# eagle-v1_0.net
KiCad netlist of a schematic drawn in EAGLE
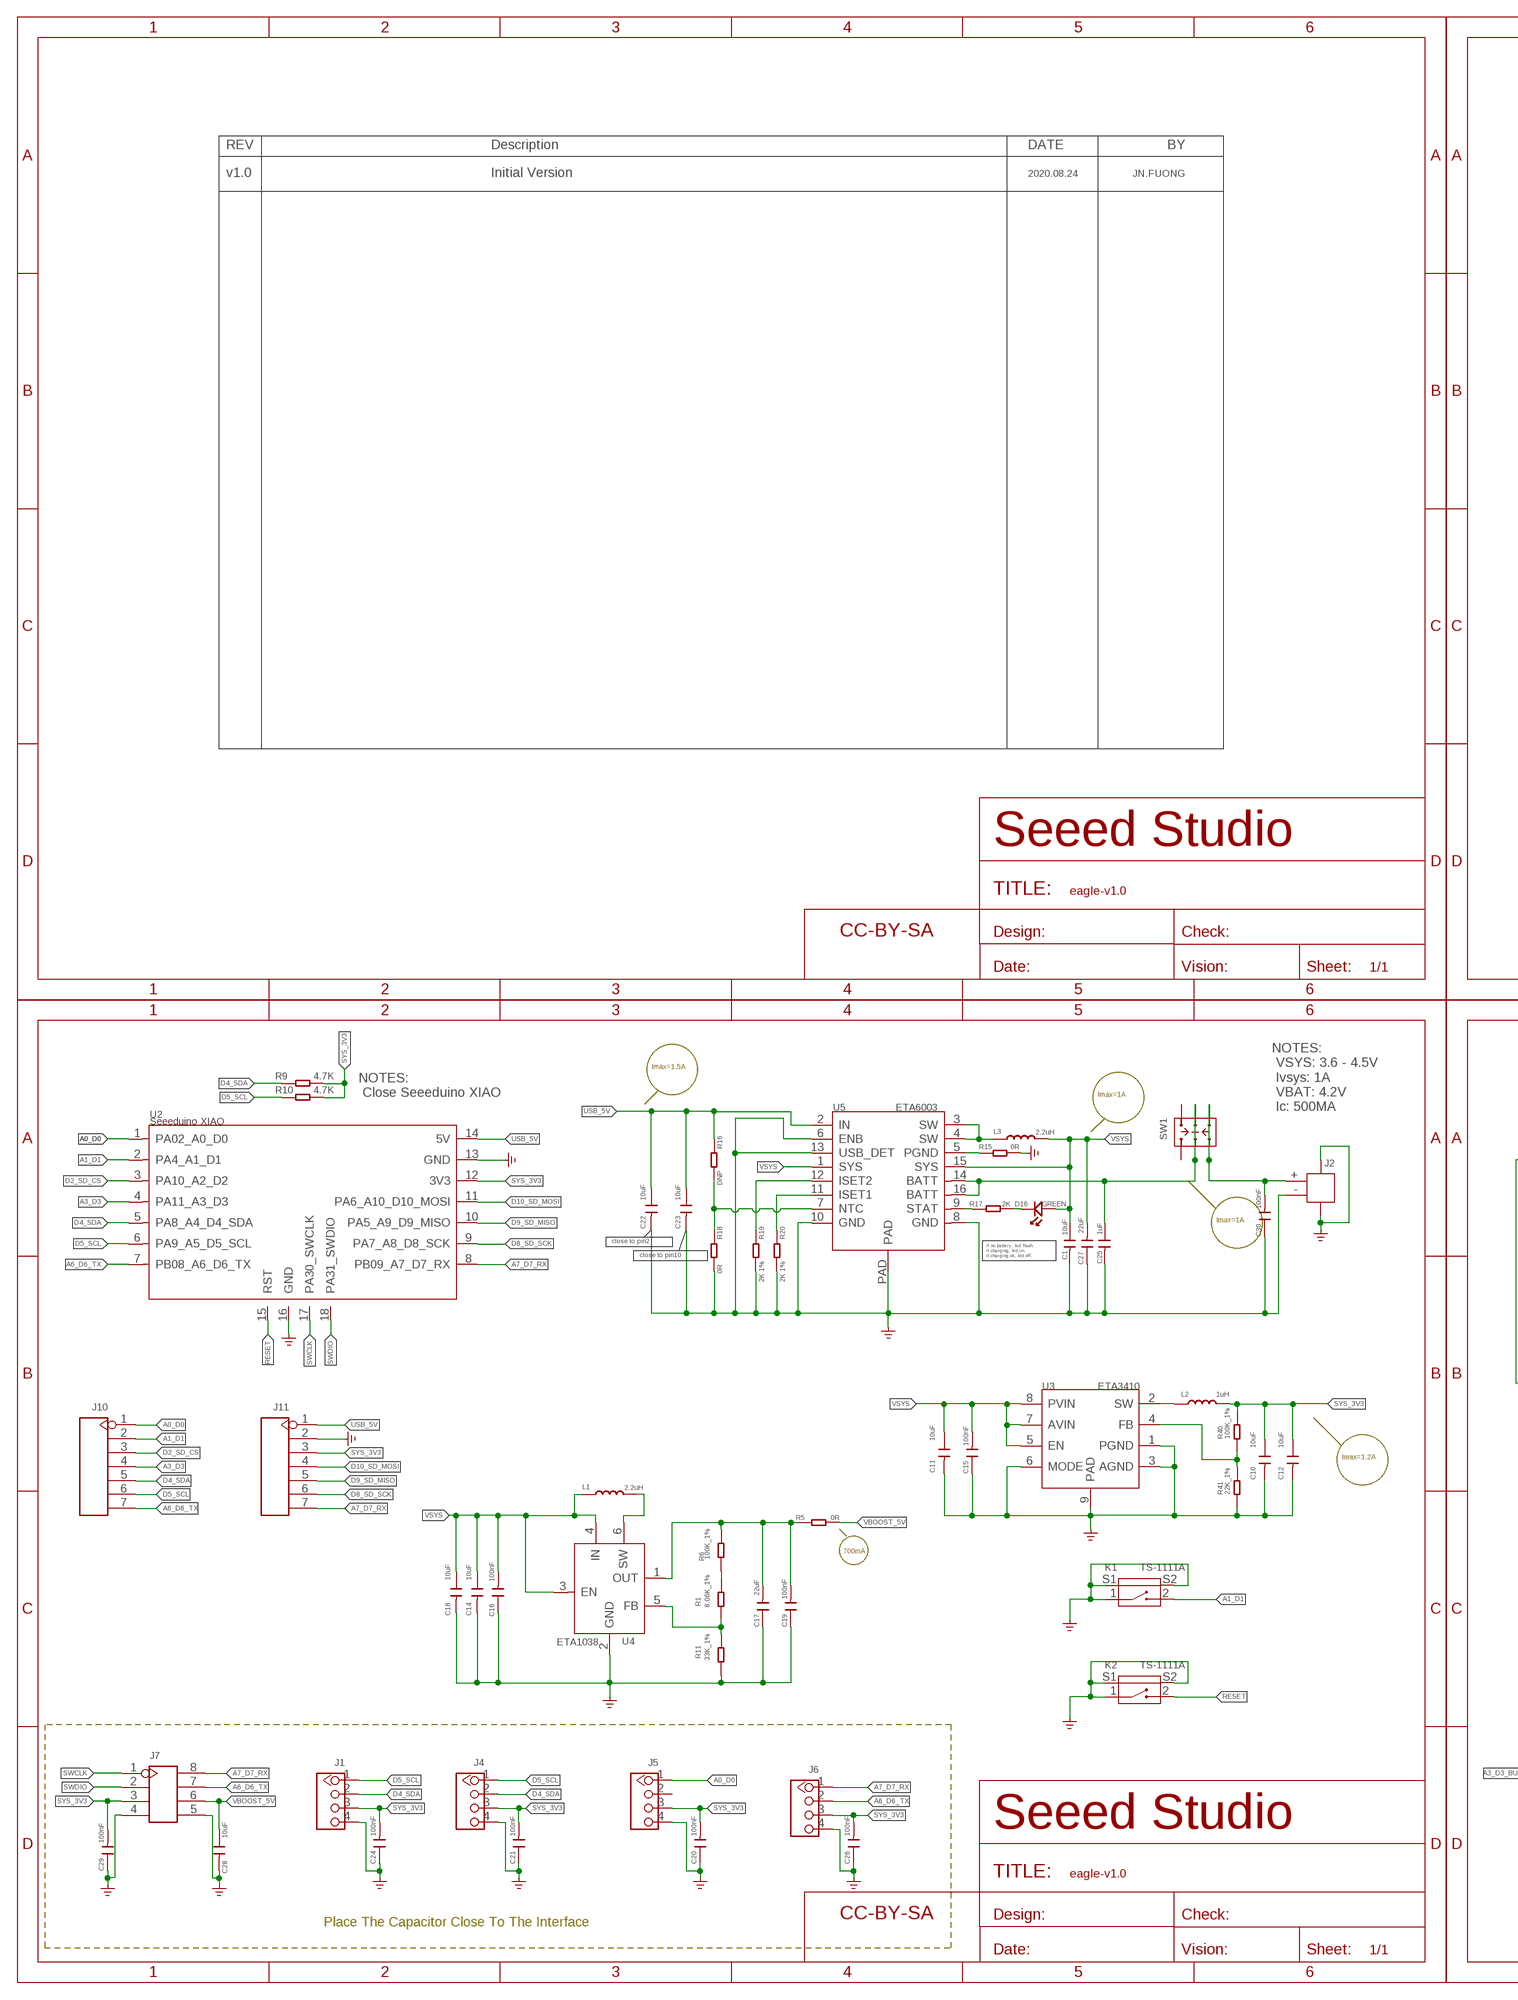
[diagram p0: schematic, sheet 1, part 1 of 2]
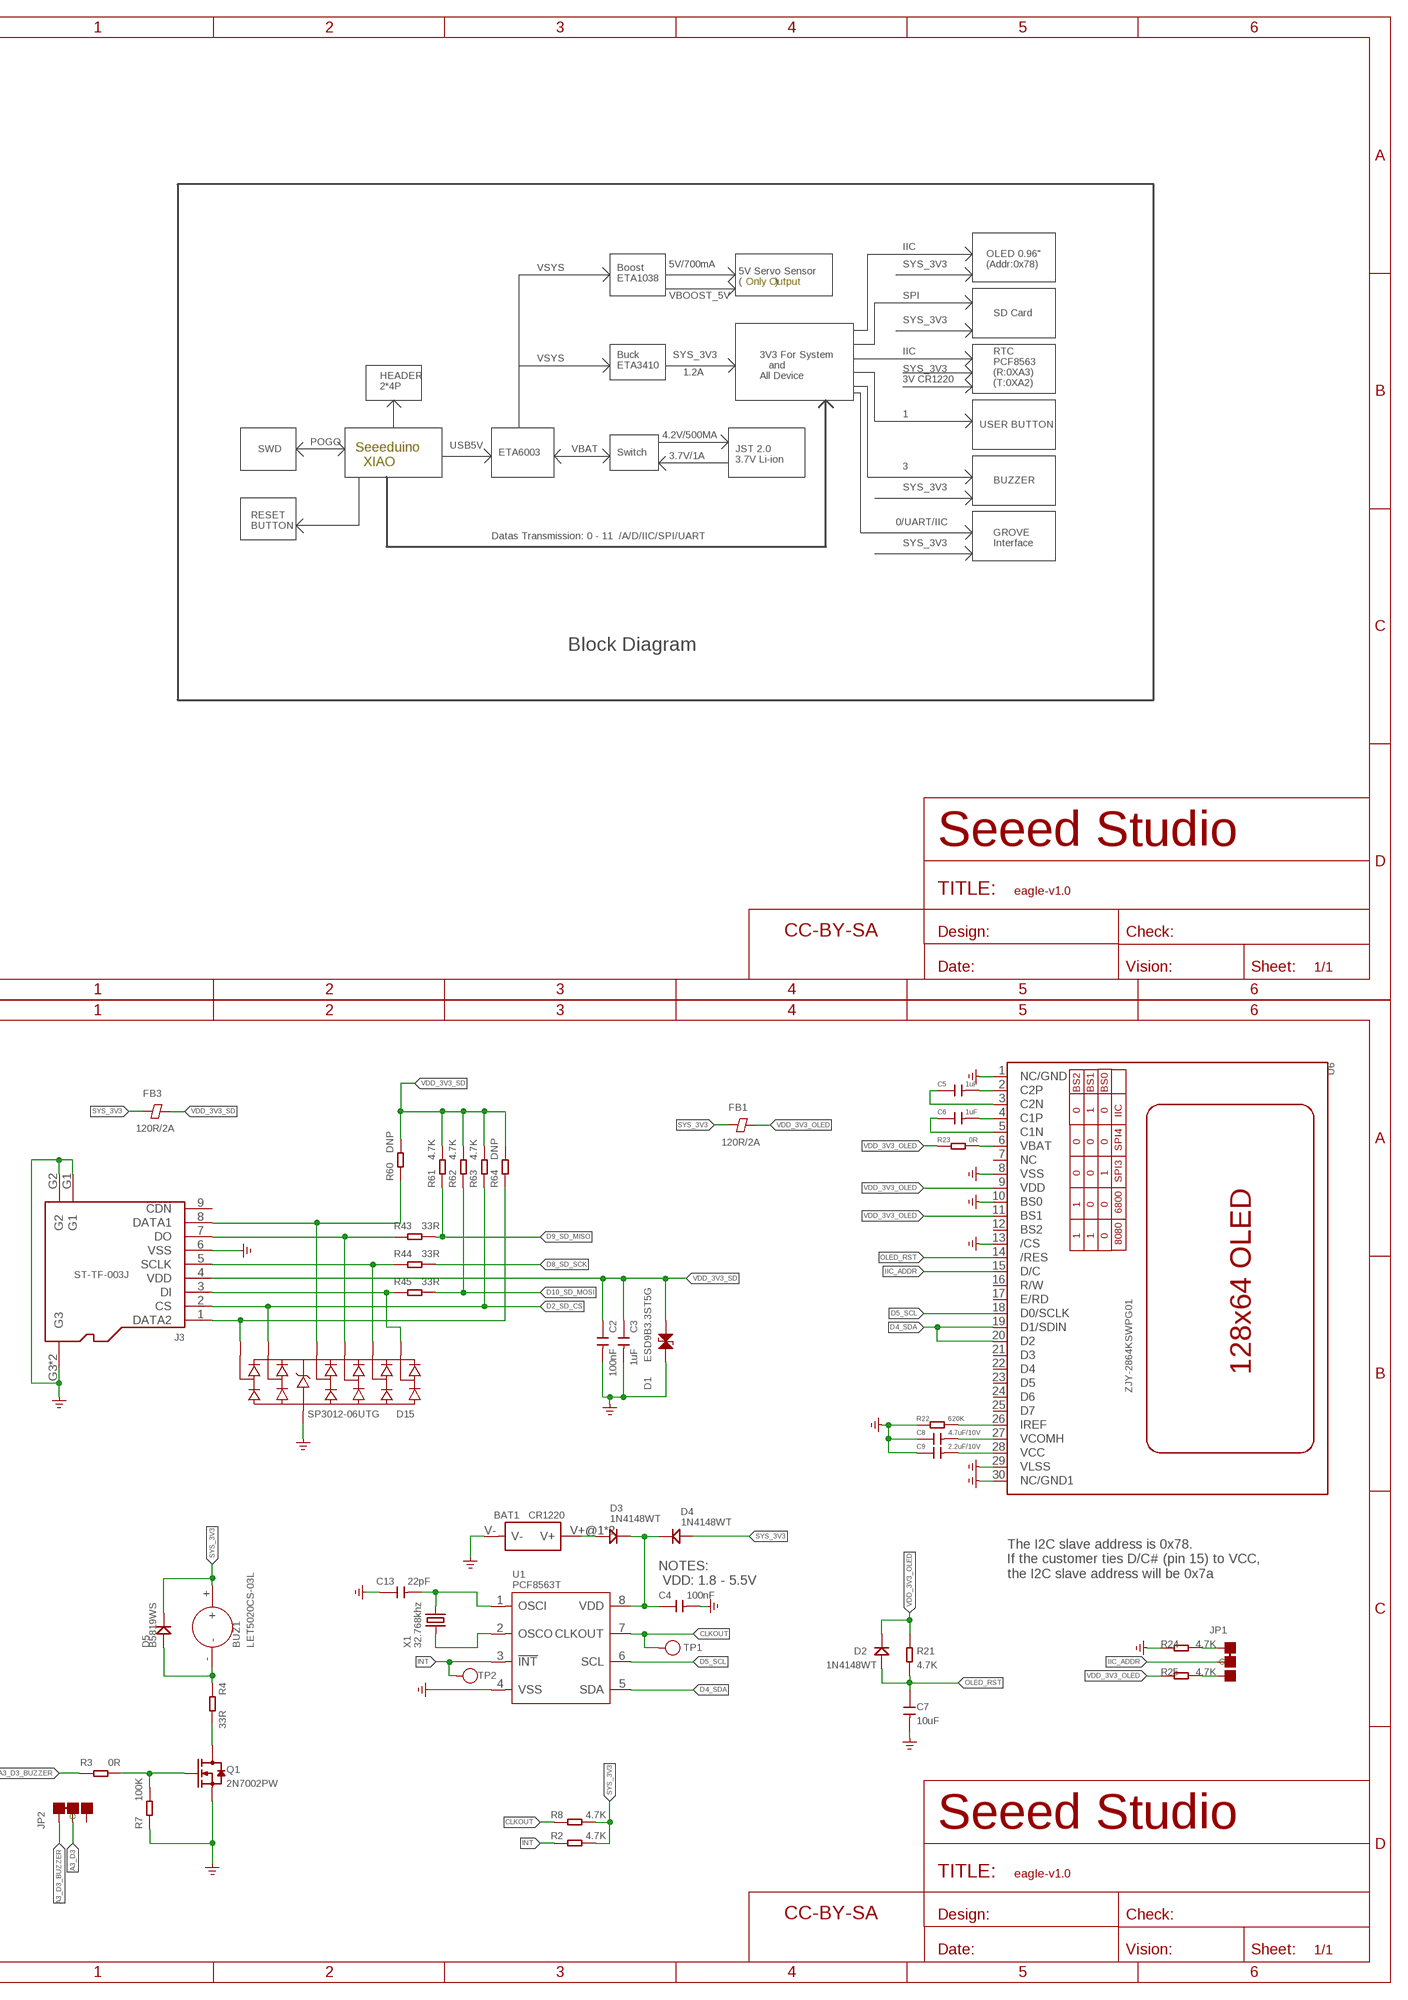
[diagram p1: schematic, sheet 1, part 2 of 2]

(export (version "E")
  (design (tool "Eeschema 10.0.6"))
  (components
    (comp (ref "BAT1")
      (value "CR1220")
      (footprint "eagle-import:BAT2P-SMD-13.2X12.1X3.2MM")
      (libsource (lib "eagle-import") (part "BAT-HOLDER-KST-1206"))
    )
    (comp (ref "BUZ1")
      (value "LET5020CS-03L")
      (footprint "eagle-import:BZ3-SMD-5.0X5.0X2.5MM")
      (libsource (lib "eagle-import") (part "BUZZER-312020004"))
    )
    (comp (ref "C1")
      (value "10uF")
      (footprint "eagle-import:C0603")
      (libsource (lib "eagle-import") (part "C-0603"))
    )
    (comp (ref "C2")
      (value "100nF")
      (footprint "eagle-import:C0402")
      (libsource (lib "eagle-import") (part "C-0402"))
    )
    (comp (ref "C3")
      (value "1uF")
      (footprint "eagle-import:C0402")
      (libsource (lib "eagle-import") (part "C-0402"))
    )
    (comp (ref "C4")
      (value "100nF")
      (footprint "eagle-import:C0402")
      (libsource (lib "eagle-import") (part "C-0402"))
    )
    (comp (ref "C5")
      (value "1uF")
      (footprint "eagle-import:C0402")
      (libsource (lib "eagle-import") (part "C-0402"))
    )
    (comp (ref "C6")
      (value "1uF")
      (footprint "eagle-import:C0402")
      (libsource (lib "eagle-import") (part "C-0402"))
    )
    (comp (ref "C7")
      (value "10uF")
      (footprint "eagle-import:C0603")
      (libsource (lib "eagle-import") (part "C-0603"))
    )
    (comp (ref "C8")
      (value "4.7uF/10V")
      (footprint "eagle-import:C0603")
      (libsource (lib "eagle-import") (part "C-0603"))
    )
    (comp (ref "C9")
      (value "2.2uF/10V")
      (footprint "eagle-import:C0603")
      (libsource (lib "eagle-import") (part "C-0603"))
    )
    (comp (ref "C10")
      (value "10uF")
      (footprint "eagle-import:C0603")
      (libsource (lib "eagle-import") (part "C-0603"))
    )
    (comp (ref "C11")
      (value "10uF")
      (footprint "eagle-import:C0603")
      (libsource (lib "eagle-import") (part "C-0603"))
    )
    (comp (ref "C12")
      (value "10uF")
      (footprint "eagle-import:C0603")
      (libsource (lib "eagle-import") (part "C-0603"))
    )
    (comp (ref "C13")
      (value "22pF")
      (footprint "eagle-import:C0402")
      (libsource (lib "eagle-import") (part "C-0402"))
    )
    (comp (ref "C14")
      (value "10uF")
      (footprint "eagle-import:C0603")
      (libsource (lib "eagle-import") (part "C-0603"))
    )
    (comp (ref "C15")
      (value "100nF")
      (footprint "eagle-import:C0402")
      (libsource (lib "eagle-import") (part "C-0402"))
    )
    (comp (ref "C16")
      (value "100nF")
      (footprint "eagle-import:C0402")
      (libsource (lib "eagle-import") (part "C-0402"))
    )
    (comp (ref "C17")
      (value "22uF")
      (footprint "eagle-import:C0603")
      (libsource (lib "eagle-import") (part "C-0603"))
    )
    (comp (ref "C18")
      (value "10uF")
      (footprint "eagle-import:C0603")
      (libsource (lib "eagle-import") (part "C-0603"))
    )
    (comp (ref "C19")
      (value "100nF")
      (footprint "eagle-import:C0402")
      (libsource (lib "eagle-import") (part "C-0402"))
    )
    (comp (ref "C20")
      (value "100nF")
      (footprint "eagle-import:C0402")
      (libsource (lib "eagle-import") (part "C-0402"))
    )
    (comp (ref "C21")
      (value "100nF")
      (footprint "eagle-import:C0402")
      (libsource (lib "eagle-import") (part "C-0402"))
    )
    (comp (ref "C22")
      (value "10uF")
      (footprint "eagle-import:C0603")
      (libsource (lib "eagle-import") (part "C-0603"))
    )
    (comp (ref "C23")
      (value "10uF")
      (footprint "eagle-import:C0603")
      (libsource (lib "eagle-import") (part "C-0603"))
    )
    (comp (ref "C24")
      (value "100nF")
      (footprint "eagle-import:C0402")
      (libsource (lib "eagle-import") (part "C-0402"))
    )
    (comp (ref "C25")
      (value "1uF")
      (footprint "eagle-import:C0402")
      (libsource (lib "eagle-import") (part "C-0402"))
    )
    (comp (ref "C26")
      (value "100nF")
      (footprint "eagle-import:C0402")
      (libsource (lib "eagle-import") (part "C-0402"))
    )
    (comp (ref "C27")
      (value "22uF")
      (footprint "eagle-import:C0603")
      (libsource (lib "eagle-import") (part "C-0603"))
    )
    (comp (ref "C28")
      (value "10uF")
      (footprint "eagle-import:C0603")
      (libsource (lib "eagle-import") (part "C-0603"))
    )
    (comp (ref "C29")
      (value "100nF")
      (footprint "eagle-import:C0402")
      (libsource (lib "eagle-import") (part "C-0402"))
    )
    (comp (ref "C30")
      (value "100nF")
      (footprint "eagle-import:C0603")
      (libsource (lib "eagle-import") (part "C-0603"))
    )
    (comp (ref "D1")
      (value "ESD9B3.3ST5G")
      (footprint "eagle-import:ESD-0402")
      (libsource (lib "eagle-import") (part "D-ESD-2P-DOUBLE-0402"))
    )
    (comp (ref "D2")
      (value "1N4148WT")
      (footprint "eagle-import:SOD-523")
      (libsource (lib "eagle-import") (part "DIODE'0603'"))
    )
    (comp (ref "D3")
      (value "1N4148WT")
      (footprint "eagle-import:SOD-523")
      (libsource (lib "eagle-import") (part "DIODE'0603'"))
    )
    (comp (ref "D4")
      (value "1N4148WT")
      (footprint "eagle-import:SOD-523")
      (libsource (lib "eagle-import") (part "DIODE'0603'"))
    )
    (comp (ref "D5")
      (value "B5819WS")
      (footprint "eagle-import:SOD-323")
      (libsource (lib "eagle-import") (part "DIODE'0805'"))
    )
    (comp (ref "D15")
      (value "SP3012-06UTG")
      (footprint "eagle-import:UDFN14-0.5-3.5X1.35X0.5MM")
      (libsource (lib "eagle-import") (part "D-ESD-14P"))
    )
    (comp (ref "D16")
      (value "GREEN")
      (footprint "eagle-import:LED-0402")
      (libsource (lib "eagle-import") (part "LED-0402"))
    )
    (comp (ref "FB1")
      (value "120R/2A")
      (footprint "eagle-import:F0402")
      (libsource (lib "eagle-import") (part "FERRITE-BEAD-0402"))
    )
    (comp (ref "FB3")
      (value "120R/2A")
      (footprint "eagle-import:F0402")
      (libsource (lib "eagle-import") (part "FERRITE-BEAD-0402"))
    )
    (comp (ref "FR1")
      (value "SEEEDSTUDIO-OPEN-SCH-FRAME")
      (footprint "eagle-import:SEEEDSTUDIO-PCB-FRAME")
      (libsource (lib "eagle-import") (part "SEEEDSTUDIO-OPEN-SCH-FRAME"))
    )
    (comp (ref "FR2")
      (value "SEEEDSTUDIO-OPEN-SCH-FRAME")
      (footprint "eagle-import:SEEEDSTUDIO-PCB-FRAME")
      (libsource (lib "eagle-import") (part "SEEEDSTUDIO-OPEN-SCH-FRAME"))
    )
    (comp (ref "FR3")
      (value "SEEEDSTUDIO-OPEN-SCH-FRAME")
      (footprint "eagle-import:SEEEDSTUDIO-PCB-FRAME")
      (libsource (lib "eagle-import") (part "SEEEDSTUDIO-OPEN-SCH-FRAME"))
    )
    (comp (ref "FR5")
      (value "SEEEDSTUDIO-OPEN-SCH-FRAME")
      (footprint "eagle-import:SEEEDSTUDIO-PCB-FRAME")
      (libsource (lib "eagle-import") (part "SEEEDSTUDIO-OPEN-SCH-FRAME"))
    )
    (comp (ref "J1")
      (value "GROVE-CONNECTOR-DIP-320110034")
      (footprint "eagle-import:HW4-2.0-90D")
      (libsource (lib "eagle-import") (part "GROVE-CONNECTOR-DIP-320110034"))
    )
    (comp (ref "J2")
      (value "JST-2P-SMD'2.0'")
      (footprint "eagle-import:HW2-SMD-2.0-90D")
      (libsource (lib "eagle-import") (part "JST-2P-SMD'2.0'"))
    )
    (comp (ref "J3")
      (value "ST-TF-003J")
      (footprint "eagle-import:MICRO-SD9+4P-SMD-16.1X14.5X1.85MM")
      (libsource (lib "eagle-import") (part "MICRO-SD-CARD-HOLDER-9P-320090000"))
    )
    (comp (ref "J4")
      (value "GROVE-CONNECTOR-DIP-320110034")
      (footprint "eagle-import:HW4-2.0-90D")
      (libsource (lib "eagle-import") (part "GROVE-CONNECTOR-DIP-320110034"))
    )
    (comp (ref "J5")
      (value "GROVE-CONNECTOR-DIP-320110034")
      (footprint "eagle-import:HW4-2.0-90D")
      (libsource (lib "eagle-import") (part "GROVE-CONNECTOR-DIP-320110034"))
    )
    (comp (ref "J6")
      (value "GROVE-CONNECTOR-DIP-320110034")
      (footprint "eagle-import:HW4-2.0-90D")
      (libsource (lib "eagle-import") (part "GROVE-CONNECTOR-DIP-320110034"))
    )
    (comp (ref "J7")
      (value "HEADER-2X4P-2.54-SMD")
      (footprint "eagle-import:H2X4-SMD-2.54")
      (libsource (lib "eagle-import") (part "HEADER-2X4P-2.54-SMD"))
    )
    (comp (ref "J10")
      (value "HEADER-7P-2.54")
      (footprint "eagle-import:H7-2.54")
      (libsource (lib "eagle-import") (part "HEADER-7P-2.54"))
    )
    (comp (ref "J11")
      (value "HEADER-7P-2.54")
      (footprint "eagle-import:H7-2.54")
      (libsource (lib "eagle-import") (part "HEADER-7P-2.54"))
    )
    (comp (ref "JP1")
      (value "JP-3P-SHORT")
      (footprint "eagle-import:3P-SMD-SHORT")
      (libsource (lib "eagle-import") (part "JP-3P-SHORT"))
    )
    (comp (ref "JP2")
      (value "JP-3P-SHORT")
      (footprint "eagle-import:3P-SMD-SHORT")
      (libsource (lib "eagle-import") (part "JP-3P-SHORT"))
    )
    (comp (ref "K1")
      (value "TS-1111A")
      (footprint "eagle-import:SW4-SMD-4.5X3.8X1.8MM-90D")
      (libsource (lib "eagle-import") (part "BUTTON-2+2P'HQ-TP-1100A'"))
    )
    (comp (ref "K2")
      (value "TS-1111A")
      (footprint "eagle-import:SW4-SMD-4.5X3.8X1.8MM-90D")
      (libsource (lib "eagle-import") (part "BUTTON-2+2P'HQ-TP-1100A'"))
    )
    (comp (ref "L1")
      (value "2.2uH")
      (footprint "eagle-import:L0806")
      (libsource (lib "eagle-import") (part "INDUCTOR/FERRITE-BEAD'0806'"))
    )
    (comp (ref "L2")
      (value "1uH")
      (footprint "eagle-import:L201610")
      (libsource (lib "eagle-import") (part "L-MPM201610SR33_T"))
    )
    (comp (ref "L3")
      (value "2.2uH")
      (footprint "eagle-import:L0806")
      (libsource (lib "eagle-import") (part "INDUCTOR/FERRITE-BEAD'0806'"))
    )
    (comp (ref "Q1")
      (value "2N7002PW")
      (footprint "eagle-import:SOT-323")
      (libsource (lib "eagle-import") (part "MOSFET-N-SI1304BDL"))
    )
    (comp (ref "R1")
      (value "8.06K_1%")
      (footprint "eagle-import:R0402")
      (libsource (lib "eagle-import") (part "R-0402"))
    )
    (comp (ref "R2")
      (value "4.7K")
      (footprint "eagle-import:R0402")
      (libsource (lib "eagle-import") (part "R-0402"))
    )
    (comp (ref "R3")
      (value "0R")
      (footprint "eagle-import:R0402")
      (libsource (lib "eagle-import") (part "R-0402"))
    )
    (comp (ref "R4")
      (value "33R")
      (footprint "eagle-import:R0402")
      (libsource (lib "eagle-import") (part "R-0402"))
    )
    (comp (ref "R5")
      (value "0R")
      (footprint "eagle-import:R0603")
      (libsource (lib "eagle-import") (part "R-0603"))
    )
    (comp (ref "R6")
      (value "100K_1%")
      (footprint "eagle-import:R0402")
      (libsource (lib "eagle-import") (part "R-0402"))
    )
    (comp (ref "R7")
      (value "100K")
      (footprint "eagle-import:R0402")
      (libsource (lib "eagle-import") (part "R-0402"))
    )
    (comp (ref "R8")
      (value "4.7K")
      (footprint "eagle-import:R0402")
      (libsource (lib "eagle-import") (part "R-0402"))
    )
    (comp (ref "R9")
      (value "4.7K")
      (footprint "eagle-import:R0402")
      (libsource (lib "eagle-import") (part "R-0402"))
    )
    (comp (ref "R10")
      (value "4.7K")
      (footprint "eagle-import:R0402")
      (libsource (lib "eagle-import") (part "R-0402"))
    )
    (comp (ref "R11")
      (value "33K_1%")
      (footprint "eagle-import:R0402")
      (libsource (lib "eagle-import") (part "R-0402"))
    )
    (comp (ref "R15")
      (value "0R")
      (footprint "eagle-import:R0402")
      (libsource (lib "eagle-import") (part "R-0402"))
    )
    (comp (ref "R16")
      (value "DNP")
      (footprint "eagle-import:R0402")
      (libsource (lib "eagle-import") (part "R-0402"))
    )
    (comp (ref "R17")
      (value "2K")
      (footprint "eagle-import:R0402")
      (libsource (lib "eagle-import") (part "R-0402"))
    )
    (comp (ref "R18")
      (value "0R")
      (footprint "eagle-import:R0402")
      (libsource (lib "eagle-import") (part "R-0402"))
    )
    (comp (ref "R19")
      (value "2K 1%")
      (footprint "eagle-import:R0402")
      (libsource (lib "eagle-import") (part "R-0402"))
    )
    (comp (ref "R20")
      (value "2K 1%")
      (footprint "eagle-import:R0402")
      (libsource (lib "eagle-import") (part "R-0402"))
    )
    (comp (ref "R21")
      (value "4.7K")
      (footprint "eagle-import:R0402")
      (libsource (lib "eagle-import") (part "R-0402"))
    )
    (comp (ref "R22")
      (value "620K")
      (footprint "eagle-import:R0402")
      (libsource (lib "eagle-import") (part "R-0402"))
    )
    (comp (ref "R23")
      (value "0R")
      (footprint "eagle-import:R0402")
      (libsource (lib "eagle-import") (part "R-0402"))
    )
    (comp (ref "R24")
      (value "4.7K")
      (footprint "eagle-import:R0402")
      (libsource (lib "eagle-import") (part "R-0402"))
    )
    (comp (ref "R25")
      (value "4.7K")
      (footprint "eagle-import:R0402")
      (libsource (lib "eagle-import") (part "R-0402"))
    )
    (comp (ref "R40")
      (value "100K_1%")
      (footprint "eagle-import:R0402")
      (libsource (lib "eagle-import") (part "R-0402"))
    )
    (comp (ref "R41")
      (value "22K_1%")
      (footprint "eagle-import:R0402")
      (libsource (lib "eagle-import") (part "R-0402"))
    )
    (comp (ref "R43")
      (value "33R")
      (footprint "eagle-import:R0402")
      (libsource (lib "eagle-import") (part "R-0402"))
    )
    (comp (ref "R44")
      (value "33R")
      (footprint "eagle-import:R0402")
      (libsource (lib "eagle-import") (part "R-0402"))
    )
    (comp (ref "R45")
      (value "33R")
      (footprint "eagle-import:R0402")
      (libsource (lib "eagle-import") (part "R-0402"))
    )
    (comp (ref "R60")
      (value "DNP")
      (footprint "eagle-import:R0402")
      (libsource (lib "eagle-import") (part "R-0402"))
    )
    (comp (ref "R61")
      (value "4.7K")
      (footprint "eagle-import:R0402")
      (libsource (lib "eagle-import") (part "R-0402"))
    )
    (comp (ref "R62")
      (value "4.7K")
      (footprint "eagle-import:R0402")
      (libsource (lib "eagle-import") (part "R-0402"))
    )
    (comp (ref "R63")
      (value "4.7K")
      (footprint "eagle-import:R0402")
      (libsource (lib "eagle-import") (part "R-0402"))
    )
    (comp (ref "R64")
      (value "DNP")
      (footprint "eagle-import:R0402")
      (libsource (lib "eagle-import") (part "R-0402"))
    )
    (comp (ref "SW1")
      (value "SWITCH-2CH-6P-311030004")
      (footprint "eagle-import:SW6-2.54-9.0X3.5X3.2MM-90D")
      (libsource (lib "eagle-import") (part "SWITCH-2CH-6P-311030004"))
    )
    (comp (ref "TP1")
      (value "TEST-POINT'4545'")
      (footprint "eagle-import:TP-D45MIL")
      (fields (field (name "PARTNO") "DNP"))
      (libsource (lib "eagle-import") (part "TEST-POINT'4545'"))
    )
    (comp (ref "TP2")
      (value "TEST-POINT'4545'")
      (footprint "eagle-import:TP-D45MIL")
      (fields (field (name "PARTNO") "DNP"))
      (libsource (lib "eagle-import") (part "TEST-POINT'4545'"))
    )
    (comp (ref "U1")
      (value "PCF8563T")
      (footprint "eagle-import:SOP8-1.27-5X3.9MM")
      (libsource (lib "eagle-import") (part "RTC-PCF8563T"))
    )
    (comp (ref "U2")
      (value "Seeeduino XIAO")
      (footprint "eagle-import:MOUDLE14P-2.54-21X17.8MM-TEST")
      (libsource (lib "eagle-import") (part "MOUDLE-SEEEDUINO-XIAO-TEST-DIP"))
    )
    (comp (ref "U3")
      (value "ETA3410")
      (footprint "eagle-import:DFN8G-0.5-2X2MM")
      (libsource (lib "eagle-import") (part "CONVERTER-ETA3410"))
    )
    (comp (ref "U4")
      (value "ETA1038")
      (footprint "eagle-import:SOT-23-6")
      (libsource (lib "eagle-import") (part "CONVERTER-ETA1038"))
    )
    (comp (ref "U5")
      (value "ETA6003")
      (footprint "eagle-import:QFN16GA-0.5-3X3MM")
      (libsource (lib "eagle-import") (part "PMIC-ETA6003-310990023"))
    )
    (comp (ref "U6")
      (value "ZJY-2864KSWPG01")
      (footprint "eagle-import:OLED30P-0.7-24.74X16.9MM")
      (libsource (lib "eagle-import") (part "OLED-12864-30P"))
    )
    (comp (ref "X1")
      (value "32.768khz")
      (footprint "eagle-import:X2-SMD-L2.0X1.2X0.55MM")
      (libsource (lib "eagle-import") (part "CRYSTAL-2P'NX2012SA'"))
    )
  )
  (nets
    (net (code "1") (name "A0_D0") (class "Default")
      (node (ref "J10") (pin "1") (pinfunction "1_1") (pintype "bidirectional"))
      (node (ref "J5") (pin "1") (pinfunction "1_1") (pintype "bidirectional"))
      (node (ref "U2") (pin "1") (pinfunction "PA02_A0_D0_1") (pintype "bidirectional"))
    )
    (net (code "2") (name "A1_D1") (class "Default")
      (node (ref "J10") (pin "2") (pinfunction "2_2") (pintype "bidirectional"))
      (node (ref "K1") (pin "2") (pinfunction "2_2") (pintype "bidirectional"))
      (node (ref "U2") (pin "2") (pinfunction "PA4_A1_D1_2") (pintype "bidirectional"))
    )
    (net (code "3") (name "A3_D3") (class "Default")
      (node (ref "J10") (pin "4") (pinfunction "4_4") (pintype "bidirectional"))
      (node (ref "JP2") (pin "MM") (pinfunction "C_MM") (pintype "bidirectional"))
      (node (ref "U2") (pin "4") (pinfunction "PA11_A3_D3_4") (pintype "bidirectional"))
    )
    (net (code "4") (name "A3_D3_BUZZER") (class "Default")
      (node (ref "JP2") (pin "11") (pinfunction "L_11") (pintype "bidirectional"))
      (node (ref "R3") (pin "1") (pinfunction "1_1") (pintype "passive"))
    )
    (net (code "5") (name "A6_D6_TX") (class "Default")
      (node (ref "J10") (pin "7") (pinfunction "7_7") (pintype "bidirectional"))
      (node (ref "J6") (pin "2") (pinfunction "2_2") (pintype "bidirectional"))
      (node (ref "J7") (pin "7") (pinfunction "7_7") (pintype "bidirectional"))
      (node (ref "U2") (pin "7") (pinfunction "PB08_A6_D6_TX_7") (pintype "bidirectional"))
    )
    (net (code "6") (name "A7_D7_RX") (class "Default")
      (node (ref "J11") (pin "7") (pinfunction "7_7") (pintype "bidirectional"))
      (node (ref "J6") (pin "1") (pinfunction "1_1") (pintype "bidirectional"))
      (node (ref "J7") (pin "8") (pinfunction "8_8") (pintype "bidirectional"))
      (node (ref "U2") (pin "8") (pinfunction "PB09_A7_D7_RX_8") (pintype "bidirectional"))
    )
    (net (code "7") (name "CLKOUT") (class "Default")
      (node (ref "R8") (pin "1") (pinfunction "1_1") (pintype "passive"))
      (node (ref "TP1") (pin "T") (pinfunction "T_T") (pintype "bidirectional"))
      (node (ref "U1") (pin "7") (pinfunction "CLKOUT_7") (pintype "bidirectional"))
    )
    (net (code "8") (name "D2_SD_CS") (class "Default")
      (node (ref "D15") (pin "6") (pinfunction "9_6") (pintype "bidirectional"))
      (node (ref "D15") (pin "9") (pinfunction "9_9") (pintype "bidirectional"))
      (node (ref "J10") (pin "3") (pinfunction "3_3") (pintype "bidirectional"))
      (node (ref "J3") (pin "2") (pinfunction "CS_2") (pintype "bidirectional"))
      (node (ref "R63") (pin "1") (pinfunction "1_1") (pintype "passive"))
      (node (ref "U2") (pin "3") (pinfunction "PA10_A2_D2_3") (pintype "bidirectional"))
    )
    (net (code "9") (name "D4_SDA") (class "Default")
      (node (ref "J1") (pin "2") (pinfunction "2_2") (pintype "bidirectional"))
      (node (ref "J10") (pin "5") (pinfunction "5_5") (pintype "bidirectional"))
      (node (ref "J4") (pin "2") (pinfunction "2_2") (pintype "bidirectional"))
      (node (ref "R9") (pin "1") (pinfunction "1_1") (pintype "passive"))
      (node (ref "U1") (pin "5") (pinfunction "SDA_5") (pintype "bidirectional"))
      (node (ref "U2") (pin "5") (pinfunction "PA8_A4_D4_SDA_5") (pintype "bidirectional"))
      (node (ref "U6") (pin "19") (pinfunction "D1/SDIN_19") (pintype "bidirectional"))
      (node (ref "U6") (pin "20") (pinfunction "D2_20") (pintype "input"))
    )
    (net (code "10") (name "D5_SCL") (class "Default")
      (node (ref "J1") (pin "1") (pinfunction "1_1") (pintype "bidirectional"))
      (node (ref "J10") (pin "6") (pinfunction "6_6") (pintype "bidirectional"))
      (node (ref "J4") (pin "1") (pinfunction "1_1") (pintype "bidirectional"))
      (node (ref "R10") (pin "1") (pinfunction "1_1") (pintype "passive"))
      (node (ref "U1") (pin "6") (pinfunction "SCL_6") (pintype "bidirectional"))
      (node (ref "U2") (pin "6") (pinfunction "PA9_A5_D5_SCL_6") (pintype "bidirectional"))
      (node (ref "U6") (pin "18") (pinfunction "D0/SCLK_18") (pintype "bidirectional"))
    )
    (net (code "11") (name "D8_SD_SCK") (class "Default")
      (node (ref "J11") (pin "6") (pinfunction "6_6") (pintype "bidirectional"))
      (node (ref "R44") (pin "2") (pinfunction "2_2") (pintype "passive"))
      (node (ref "U2") (pin "9") (pinfunction "PA7_A8_D8_SCK_9") (pintype "bidirectional"))
    )
    (net (code "12") (name "D9_SD_MISO") (class "Default")
      (node (ref "J11") (pin "5") (pinfunction "5_5") (pintype "bidirectional"))
      (node (ref "R43") (pin "2") (pinfunction "2_2") (pintype "passive"))
      (node (ref "R61") (pin "1") (pinfunction "1_1") (pintype "passive"))
      (node (ref "U2") (pin "10") (pinfunction "PA5_A9_D9_MISO_10") (pintype "bidirectional"))
    )
    (net (code "13") (name "D10_SD_MOSI") (class "Default")
      (node (ref "J11") (pin "4") (pinfunction "4_4") (pintype "bidirectional"))
      (node (ref "R45") (pin "2") (pinfunction "2_2") (pintype "passive"))
      (node (ref "R62") (pin "1") (pinfunction "1_1") (pintype "passive"))
      (node (ref "U2") (pin "11") (pinfunction "PA6_A10_D10_MOSI_11") (pintype "bidirectional"))
    )
    (net (code "14") (name "GND_POWER") (class "Default")
      (node (ref "BAT1") (pin "V-") (pinfunction "V-_V-") (pintype "bidirectional"))
      (node (ref "C1") (pin "2") (pinfunction "2_2") (pintype "passive"))
      (node (ref "C10") (pin "2") (pinfunction "2_2") (pintype "passive"))
      (node (ref "C11") (pin "2") (pinfunction "2_2") (pintype "passive"))
      (node (ref "C12") (pin "2") (pinfunction "2_2") (pintype "passive"))
      (node (ref "C13") (pin "1") (pinfunction "1_1") (pintype "passive"))
      (node (ref "C14") (pin "2") (pinfunction "2_2") (pintype "passive"))
      (node (ref "C15") (pin "1") (pinfunction "1_1") (pintype "passive"))
      (node (ref "C16") (pin "1") (pinfunction "1_1") (pintype "passive"))
      (node (ref "C17") (pin "1") (pinfunction "1_1") (pintype "passive"))
      (node (ref "C18") (pin "2") (pinfunction "2_2") (pintype "passive"))
      (node (ref "C19") (pin "1") (pinfunction "1_1") (pintype "passive"))
      (node (ref "C2") (pin "2") (pinfunction "2_2") (pintype "passive"))
      (node (ref "C20") (pin "1") (pinfunction "1_1") (pintype "passive"))
      (node (ref "C21") (pin "1") (pinfunction "1_1") (pintype "passive"))
      (node (ref "C22") (pin "2") (pinfunction "2_2") (pintype "passive"))
      (node (ref "C23") (pin "2") (pinfunction "2_2") (pintype "passive"))
      (node (ref "C24") (pin "1") (pinfunction "1_1") (pintype "passive"))
      (node (ref "C25") (pin "2") (pinfunction "2_2") (pintype "passive"))
      (node (ref "C26") (pin "1") (pinfunction "1_1") (pintype "passive"))
      (node (ref "C27") (pin "1") (pinfunction "1_1") (pintype "passive"))
      (node (ref "C28") (pin "2") (pinfunction "2_2") (pintype "passive"))
      (node (ref "C29") (pin "1") (pinfunction "1_1") (pintype "passive"))
      (node (ref "C3") (pin "2") (pinfunction "2_2") (pintype "passive"))
      (node (ref "C30") (pin "1") (pinfunction "1_1") (pintype "passive"))
      (node (ref "C4") (pin "2") (pinfunction "2_2") (pintype "passive"))
      (node (ref "C7") (pin "2") (pinfunction "2_2") (pintype "passive"))
      (node (ref "C8") (pin "1") (pinfunction "1_1") (pintype "passive"))
      (node (ref "C9") (pin "1") (pinfunction "1_1") (pintype "passive"))
      (node (ref "D1") (pin "1") (pinfunction "1_1") (pintype "bidirectional"))
      (node (ref "D15") (pin "10") (pinfunction "10_10") (pintype "bidirectional"))
      (node (ref "D15") (pin "5") (pinfunction "10_5") (pintype "bidirectional"))
      (node (ref "J1") (pin "4") (pinfunction "4_4") (pintype "bidirectional"))
      (node (ref "J11") (pin "2") (pinfunction "2_2") (pintype "bidirectional"))
      (node (ref "J2") (pin "-") (pinfunction "2_-") (pintype "bidirectional"))
      (node (ref "J2") (pin "3") (pinfunction "3_3") (pintype "bidirectional"))
      (node (ref "J2") (pin "4") (pinfunction "4_4") (pintype "bidirectional"))
      (node (ref "J3") (pin "6") (pinfunction "VSS_6") (pintype "bidirectional"))
      (node (ref "J3") (pin "G1") (pinfunction "G1_G1") (pintype "bidirectional"))
      (node (ref "J3") (pin "G2") (pinfunction "G2_G2") (pintype "bidirectional"))
      (node (ref "J3") (pin "G3") (pinfunction "G3_G3") (pintype "bidirectional"))
      (node (ref "J3") (pin "G4") (pinfunction "G3_G4") (pintype "bidirectional"))
      (node (ref "J4") (pin "4") (pinfunction "4_4") (pintype "bidirectional"))
      (node (ref "J5") (pin "4") (pinfunction "4_4") (pintype "bidirectional"))
      (node (ref "J6") (pin "4") (pinfunction "4_4") (pintype "bidirectional"))
      (node (ref "J7") (pin "4") (pinfunction "4_4") (pintype "bidirectional"))
      (node (ref "J7") (pin "5") (pinfunction "5_5") (pintype "bidirectional"))
      (node (ref "K1") (pin "1") (pinfunction "1_1") (pintype "bidirectional"))
      (node (ref "K1") (pin "S1") (pinfunction "S1_S1") (pintype "bidirectional"))
      (node (ref "K1") (pin "S2") (pinfunction "S2_S2") (pintype "bidirectional"))
      (node (ref "K2") (pin "1") (pinfunction "1_1") (pintype "bidirectional"))
      (node (ref "K2") (pin "S1") (pinfunction "S1_S1") (pintype "bidirectional"))
      (node (ref "K2") (pin "S2") (pinfunction "S2_S2") (pintype "bidirectional"))
      (node (ref "Q1") (pin "2") (pinfunction "S_2") (pintype "passive"))
      (node (ref "R11") (pin "2") (pinfunction "2_2") (pintype "passive"))
      (node (ref "R15") (pin "2") (pinfunction "2_2") (pintype "passive"))
      (node (ref "R18") (pin "2") (pinfunction "2_2") (pintype "passive"))
      (node (ref "R19") (pin "2") (pinfunction "2_2") (pintype "passive"))
      (node (ref "R20") (pin "2") (pinfunction "2_2") (pintype "passive"))
      (node (ref "R22") (pin "2") (pinfunction "2_2") (pintype "passive"))
      (node (ref "R24") (pin "1") (pinfunction "1_1") (pintype "passive"))
      (node (ref "R41") (pin "1") (pinfunction "1_1") (pintype "passive"))
      (node (ref "R7") (pin "1") (pinfunction "1_1") (pintype "passive"))
      (node (ref "U1") (pin "4") (pinfunction "VSS_4") (pintype "bidirectional"))
      (node (ref "U2") (pin "13") (pinfunction "GND_13") (pintype "bidirectional"))
      (node (ref "U2") (pin "16") (pinfunction "GND_16") (pintype "bidirectional"))
      (node (ref "U3") (pin "1") (pinfunction "PGND_1") (pintype "bidirectional"))
      (node (ref "U3") (pin "3") (pinfunction "AGND_3") (pintype "bidirectional"))
      (node (ref "U3") (pin "6") (pinfunction "MODE_6") (pintype "bidirectional"))
      (node (ref "U3") (pin "9") (pinfunction "PAD_9") (pintype "bidirectional"))
      (node (ref "U4") (pin "2") (pinfunction "GND_2") (pintype "bidirectional"))
      (node (ref "U5") (pin "10") (pinfunction "GND_10") (pintype "bidirectional"))
      (node (ref "U5") (pin "13") (pinfunction "USB_DET_13") (pintype "bidirectional"))
      (node (ref "U5") (pin "6") (pinfunction "ENB_6") (pintype "bidirectional"))
      (node (ref "U5") (pin "8") (pinfunction "GND_8") (pintype "bidirectional"))
      (node (ref "U5") (pin "PAD") (pinfunction "PAD_PAD") (pintype "bidirectional"))
      (node (ref "U6") (pin "1") (pinfunction "NC/GND_1") (pintype "input"))
      (node (ref "U6") (pin "10") (pinfunction "BS0_10") (pintype "input"))
      (node (ref "U6") (pin "13") (pinfunction "/CS_13") (pintype "input"))
      (node (ref "U6") (pin "29") (pinfunction "VLSS_29") (pintype "power_in"))
      (node (ref "U6") (pin "30") (pinfunction "NC/GND1_30") (pintype "input"))
      (node (ref "U6") (pin "8") (pinfunction "VSS_8") (pintype "power_in"))
    )
    (net (code "15") (name "IIC_ADDR") (class "Default")
      (node (ref "JP1") (pin "MM") (pinfunction "C_MM") (pintype "bidirectional"))
      (node (ref "U6") (pin "15") (pinfunction "D/C_15") (pintype "input"))
    )
    (net (code "16") (name "INT") (class "Default")
      (node (ref "R2") (pin "1") (pinfunction "1_1") (pintype "passive"))
      (node (ref "TP2") (pin "T") (pinfunction "T_T") (pintype "bidirectional"))
      (node (ref "U1") (pin "3") (pinfunction "~{INT}_3") (pintype "bidirectional"))
    )
    (net (code "17") (name "Net-(BAT1-V+-PadV+@1)") (class "Default")
      (node (ref "BAT1") (pin "V+@1") (pinfunction "V+_V+@1") (pintype "bidirectional"))
      (node (ref "BAT1") (pin "V+@2") (pinfunction "V+_V+@2") (pintype "bidirectional"))
      (node (ref "D3") (pin "+") (pinfunction "+_+") (pintype "passive"))
    )
    (net (code "18") (name "Net-(BUZ1-Pad-)") (class "Default")
      (node (ref "BUZ1") (pin "-") (pinfunction "-_-") (pintype "bidirectional"))
      (node (ref "D5") (pin "+") (pinfunction "+_+") (pintype "passive"))
      (node (ref "R4") (pin "1") (pinfunction "1_1") (pintype "passive"))
    )
    (net (code "19") (name "Net-(C25-Pad1)") (class "Default")
      (node (ref "C25") (pin "1") (pinfunction "1_1") (pintype "passive"))
      (node (ref "SW1") (pin "COM1") (pinfunction "COM1_COM1") (pintype "bidirectional"))
      (node (ref "SW1") (pin "COM2") (pinfunction "COM2_COM2") (pintype "bidirectional"))
      (node (ref "U5") (pin "14") (pinfunction "BATT_14") (pintype "bidirectional"))
      (node (ref "U5") (pin "16") (pinfunction "BATT_16") (pintype "bidirectional"))
    )
    (net (code "20") (name "Net-(D16-Pad-)") (class "Default")
      (node (ref "D16") (pin "-") (pinfunction "-_-") (pintype "passive"))
      (node (ref "R17") (pin "1") (pinfunction "1_1") (pintype "passive"))
    )
    (net (code "21") (name "Net-(J2-1)") (class "Default")
      (node (ref "C30") (pin "2") (pinfunction "2_2") (pintype "passive"))
      (node (ref "J2") (pin "+") (pinfunction "1_+") (pintype "bidirectional"))
      (node (ref "SW1") (pin "CH1B") (pinfunction "CH1B_CH1B") (pintype "bidirectional"))
      (node (ref "SW1") (pin "CH2B") (pinfunction "CH2B_CH2B") (pintype "bidirectional"))
    )
    (net (code "22") (name "Net-(J3-DATA1)") (class "Default")
      (node (ref "D15") (pin "1") (pinfunction "14_1") (pintype "bidirectional"))
      (node (ref "D15") (pin "14") (pinfunction "14_14") (pintype "bidirectional"))
      (node (ref "J3") (pin "8") (pinfunction "DATA1_8") (pintype "bidirectional"))
      (node (ref "R60") (pin "1") (pinfunction "1_1") (pintype "passive"))
    )
    (net (code "23") (name "Net-(J3-DATA2)") (class "Default")
      (node (ref "D15") (pin "7") (pinfunction "8_7") (pintype "bidirectional"))
      (node (ref "D15") (pin "8") (pinfunction "8_8") (pintype "bidirectional"))
      (node (ref "J3") (pin "1") (pinfunction "DATA2_1") (pintype "bidirectional"))
      (node (ref "R64") (pin "1") (pinfunction "1_1") (pintype "passive"))
    )
    (net (code "24") (name "Net-(J3-DI)") (class "Default")
      (node (ref "D15") (pin "11") (pinfunction "11_11") (pintype "bidirectional"))
      (node (ref "D15") (pin "4") (pinfunction "11_4") (pintype "bidirectional"))
      (node (ref "J3") (pin "3") (pinfunction "DI_3") (pintype "bidirectional"))
      (node (ref "R45") (pin "1") (pinfunction "1_1") (pintype "passive"))
    )
    (net (code "25") (name "Net-(J3-DO)") (class "Default")
      (node (ref "D15") (pin "13") (pinfunction "13_13") (pintype "bidirectional"))
      (node (ref "D15") (pin "2") (pinfunction "13_2") (pintype "bidirectional"))
      (node (ref "J3") (pin "7") (pinfunction "DO_7") (pintype "bidirectional"))
      (node (ref "R43") (pin "1") (pinfunction "1_1") (pintype "passive"))
    )
    (net (code "26") (name "Net-(J3-SCLK)") (class "Default")
      (node (ref "D15") (pin "12") (pinfunction "12_12") (pintype "bidirectional"))
      (node (ref "D15") (pin "3") (pinfunction "12_3") (pintype "bidirectional"))
      (node (ref "J3") (pin "5") (pinfunction "SCLK_5") (pintype "bidirectional"))
      (node (ref "R44") (pin "1") (pinfunction "1_1") (pintype "passive"))
    )
    (net (code "27") (name "Net-(JP1-L)") (class "Default")
      (node (ref "JP1") (pin "11") (pinfunction "L_11") (pintype "bidirectional"))
      (node (ref "R24") (pin "2") (pinfunction "2_2") (pintype "passive"))
    )
    (net (code "28") (name "Net-(JP1-R)") (class "Default")
      (node (ref "JP1") (pin "00") (pinfunction "R_00") (pintype "bidirectional"))
      (node (ref "R25") (pin "2") (pinfunction "2_2") (pintype "passive"))
    )
    (net (code "29") (name "Net-(L3-Pad1)") (class "Default")
      (node (ref "L3") (pin "1") (pinfunction "1_1") (pintype "passive"))
      (node (ref "U5") (pin "3") (pinfunction "SW_3") (pintype "bidirectional"))
      (node (ref "U5") (pin "4") (pinfunction "SW_4") (pintype "bidirectional"))
    )
    (net (code "30") (name "Net-(Q1-D)") (class "Default")
      (node (ref "Q1") (pin "3") (pinfunction "D_3") (pintype "passive"))
      (node (ref "R4") (pin "2") (pinfunction "2_2") (pintype "passive"))
    )
    (net (code "31") (name "Net-(Q1-G)") (class "Default")
      (node (ref "Q1") (pin "1") (pinfunction "G_1") (pintype "passive"))
      (node (ref "R3") (pin "2") (pinfunction "2_2") (pintype "passive"))
      (node (ref "R7") (pin "2") (pinfunction "2_2") (pintype "passive"))
    )
    (net (code "32") (name "Net-(R1-Pad1)") (class "Default")
      (node (ref "R1") (pin "1") (pinfunction "1_1") (pintype "passive"))
      (node (ref "R6") (pin "2") (pinfunction "2_2") (pintype "passive"))
    )
    (net (code "33") (name "Net-(U1-OSCI)") (class "Default")
      (node (ref "C13") (pin "2") (pinfunction "2_2") (pintype "passive"))
      (node (ref "U1") (pin "1") (pinfunction "OSCI_1") (pintype "bidirectional"))
      (node (ref "X1") (pin "2") (pinfunction "2_2") (pintype "passive"))
    )
    (net (code "34") (name "Net-(U1-OSCO)") (class "Default")
      (node (ref "U1") (pin "2") (pinfunction "OSCO_2") (pintype "bidirectional"))
      (node (ref "X1") (pin "1") (pinfunction "1_1") (pintype "passive"))
    )
    (net (code "35") (name "Net-(U1-VDD)") (class "Default")
      (node (ref "C4") (pin "1") (pinfunction "1_1") (pintype "passive"))
      (node (ref "D3") (pin "-") (pinfunction "-_-") (pintype "passive"))
      (node (ref "D4") (pin "-") (pinfunction "-_-") (pintype "passive"))
      (node (ref "U1") (pin "8") (pinfunction "VDD_8") (pintype "bidirectional"))
    )
    (net (code "36") (name "Net-(U3-FB)") (class "Default")
      (node (ref "R40") (pin "1") (pinfunction "1_1") (pintype "passive"))
      (node (ref "R41") (pin "2") (pinfunction "2_2") (pintype "passive"))
      (node (ref "U3") (pin "4") (pinfunction "FB_4") (pintype "bidirectional"))
    )
    (net (code "37") (name "Net-(U3-SW)") (class "Default")
      (node (ref "L2") (pin "1") (pinfunction "1_1") (pintype "passive"))
      (node (ref "U3") (pin "2") (pinfunction "SW_2") (pintype "bidirectional"))
    )
    (net (code "38") (name "Net-(U4-FB)") (class "Default")
      (node (ref "R1") (pin "2") (pinfunction "2_2") (pintype "passive"))
      (node (ref "R11") (pin "1") (pinfunction "1_1") (pintype "passive"))
      (node (ref "U4") (pin "5") (pinfunction "FB_5") (pintype "bidirectional"))
    )
    (net (code "39") (name "Net-(U4-OUT)") (class "Default")
      (node (ref "C17") (pin "2") (pinfunction "2_2") (pintype "passive"))
      (node (ref "C19") (pin "2") (pinfunction "2_2") (pintype "passive"))
      (node (ref "R5") (pin "2") (pinfunction "2_2") (pintype "passive"))
      (node (ref "R6") (pin "1") (pinfunction "1_1") (pintype "passive"))
      (node (ref "U4") (pin "1") (pinfunction "OUT_1") (pintype "bidirectional"))
    )
    (net (code "40") (name "Net-(U4-SW)") (class "Default")
      (node (ref "L1") (pin "2") (pinfunction "2_2") (pintype "passive"))
      (node (ref "U4") (pin "6") (pinfunction "SW_6") (pintype "bidirectional"))
    )
    (net (code "41") (name "Net-(U5-ISET1)") (class "Default")
      (node (ref "R20") (pin "1") (pinfunction "1_1") (pintype "passive"))
      (node (ref "U5") (pin "11") (pinfunction "ISET1_11") (pintype "bidirectional"))
    )
    (net (code "42") (name "Net-(U5-ISET2)") (class "Default")
      (node (ref "R19") (pin "1") (pinfunction "1_1") (pintype "passive"))
      (node (ref "U5") (pin "12") (pinfunction "ISET2_12") (pintype "bidirectional"))
    )
    (net (code "43") (name "Net-(U5-NTC)") (class "Default")
      (node (ref "R16") (pin "2") (pinfunction "2_2") (pintype "passive"))
      (node (ref "R18") (pin "1") (pinfunction "1_1") (pintype "passive"))
      (node (ref "U5") (pin "7") (pinfunction "NTC_7") (pintype "bidirectional"))
    )
    (net (code "44") (name "Net-(U5-PGND)") (class "Default")
      (node (ref "R15") (pin "1") (pinfunction "1_1") (pintype "passive"))
      (node (ref "U5") (pin "5") (pinfunction "PGND_5") (pintype "bidirectional"))
    )
    (net (code "45") (name "Net-(U5-STAT)") (class "Default")
      (node (ref "R17") (pin "2") (pinfunction "2_2") (pintype "passive"))
      (node (ref "U5") (pin "9") (pinfunction "STAT_9") (pintype "bidirectional"))
    )
    (net (code "46") (name "Net-(U6-C1N)") (class "Default")
      (node (ref "C6") (pin "1") (pinfunction "1_1") (pintype "passive"))
      (node (ref "U6") (pin "5") (pinfunction "C1N_5") (pintype "input"))
    )
    (net (code "47") (name "Net-(U6-C1P)") (class "Default")
      (node (ref "C6") (pin "2") (pinfunction "2_2") (pintype "passive"))
      (node (ref "U6") (pin "4") (pinfunction "C1P_4") (pintype "input"))
    )
    (net (code "48") (name "Net-(U6-C2N)") (class "Default")
      (node (ref "C5") (pin "1") (pinfunction "1_1") (pintype "passive"))
      (node (ref "U6") (pin "3") (pinfunction "C2N_3") (pintype "input"))
    )
    (net (code "49") (name "Net-(U6-C2P)") (class "Default")
      (node (ref "C5") (pin "2") (pinfunction "2_2") (pintype "passive"))
      (node (ref "U6") (pin "2") (pinfunction "C2P_2") (pintype "input"))
    )
    (net (code "50") (name "Net-(U6-IREF)") (class "Default")
      (node (ref "R22") (pin "1") (pinfunction "1_1") (pintype "passive"))
      (node (ref "U6") (pin "26") (pinfunction "IREF_26") (pintype "input"))
    )
    (net (code "51") (name "Net-(U6-VBAT)") (class "Default")
      (node (ref "R23") (pin "2") (pinfunction "2_2") (pintype "passive"))
      (node (ref "U6") (pin "6") (pinfunction "VBAT_6") (pintype "input"))
    )
    (net (code "52") (name "Net-(U6-VCC)") (class "Default")
      (node (ref "C9") (pin "2") (pinfunction "2_2") (pintype "passive"))
      (node (ref "U6") (pin "28") (pinfunction "VCC_28") (pintype "power_in"))
    )
    (net (code "53") (name "Net-(U6-VCOMH)") (class "Default")
      (node (ref "C8") (pin "2") (pinfunction "2_2") (pintype "passive"))
      (node (ref "U6") (pin "27") (pinfunction "VCOMH_27") (pintype "output"))
    )
    (net (code "54") (name "OLED_RST") (class "Default")
      (node (ref "C7") (pin "1") (pinfunction "1_1") (pintype "passive"))
      (node (ref "D2") (pin "+") (pinfunction "+_+") (pintype "passive"))
      (node (ref "R21") (pin "1") (pinfunction "1_1") (pintype "passive"))
      (node (ref "U6") (pin "14") (pinfunction "/RES_14") (pintype "input"))
    )
    (net (code "55") (name "RESET") (class "Default")
      (node (ref "K2") (pin "2") (pinfunction "2_2") (pintype "bidirectional"))
      (node (ref "U2") (pin "15") (pinfunction "RST_15") (pintype "bidirectional"))
    )
    (net (code "56") (name "SWCLK") (class "Default")
      (node (ref "J7") (pin "1") (pinfunction "1_1") (pintype "bidirectional"))
      (node (ref "U2") (pin "17") (pinfunction "PA30_SWCLK_17") (pintype "bidirectional"))
    )
    (net (code "57") (name "SWDIO") (class "Default")
      (node (ref "J7") (pin "2") (pinfunction "2_2") (pintype "bidirectional"))
      (node (ref "U2") (pin "18") (pinfunction "PA31_SWDIO_18") (pintype "bidirectional"))
    )
    (net (code "58") (name "SYS_3V3") (class "Default")
      (node (ref "BUZ1") (pin "+") (pinfunction "+_+") (pintype "bidirectional"))
      (node (ref "C10") (pin "1") (pinfunction "1_1") (pintype "passive"))
      (node (ref "C12") (pin "1") (pinfunction "1_1") (pintype "passive"))
      (node (ref "C20") (pin "2") (pinfunction "2_2") (pintype "passive"))
      (node (ref "C21") (pin "2") (pinfunction "2_2") (pintype "passive"))
      (node (ref "C24") (pin "2") (pinfunction "2_2") (pintype "passive"))
      (node (ref "C26") (pin "2") (pinfunction "2_2") (pintype "passive"))
      (node (ref "C29") (pin "2") (pinfunction "2_2") (pintype "passive"))
      (node (ref "D4") (pin "+") (pinfunction "+_+") (pintype "passive"))
      (node (ref "D5") (pin "-") (pinfunction "-_-") (pintype "passive"))
      (node (ref "FB1") (pin "1") (pinfunction "1_1") (pintype "bidirectional"))
      (node (ref "FB3") (pin "1") (pinfunction "1_1") (pintype "bidirectional"))
      (node (ref "J1") (pin "3") (pinfunction "3_3") (pintype "bidirectional"))
      (node (ref "J11") (pin "3") (pinfunction "3_3") (pintype "bidirectional"))
      (node (ref "J4") (pin "3") (pinfunction "3_3") (pintype "bidirectional"))
      (node (ref "J5") (pin "3") (pinfunction "3_3") (pintype "bidirectional"))
      (node (ref "J6") (pin "3") (pinfunction "3_3") (pintype "bidirectional"))
      (node (ref "J7") (pin "3") (pinfunction "3_3") (pintype "bidirectional"))
      (node (ref "L2") (pin "2") (pinfunction "2_2") (pintype "passive"))
      (node (ref "R10") (pin "2") (pinfunction "2_2") (pintype "passive"))
      (node (ref "R2") (pin "2") (pinfunction "2_2") (pintype "passive"))
      (node (ref "R40") (pin "2") (pinfunction "2_2") (pintype "passive"))
      (node (ref "R8") (pin "2") (pinfunction "2_2") (pintype "passive"))
      (node (ref "R9") (pin "2") (pinfunction "2_2") (pintype "passive"))
      (node (ref "U2") (pin "12") (pinfunction "3V3_12") (pintype "bidirectional"))
    )
    (net (code "59") (name "USB_5V") (class "Default")
      (node (ref "C22") (pin "1") (pinfunction "1_1") (pintype "passive"))
      (node (ref "C23") (pin "1") (pinfunction "1_1") (pintype "passive"))
      (node (ref "J11") (pin "1") (pinfunction "1_1") (pintype "bidirectional"))
      (node (ref "R16") (pin "1") (pinfunction "1_1") (pintype "passive"))
      (node (ref "U2") (pin "14") (pinfunction "5V_14") (pintype "bidirectional"))
      (node (ref "U5") (pin "2") (pinfunction "IN_2") (pintype "bidirectional"))
    )
    (net (code "60") (name "VBOOST_5V") (class "Default")
      (node (ref "C28") (pin "1") (pinfunction "1_1") (pintype "passive"))
      (node (ref "J7") (pin "6") (pinfunction "6_6") (pintype "bidirectional"))
      (node (ref "R5") (pin "1") (pinfunction "1_1") (pintype "passive"))
    )
    (net (code "61") (name "VDD_3V3_OLED") (class "Default")
      (node (ref "D2") (pin "-") (pinfunction "-_-") (pintype "passive"))
      (node (ref "FB1") (pin "2") (pinfunction "2_2") (pintype "bidirectional"))
      (node (ref "R21") (pin "2") (pinfunction "2_2") (pintype "passive"))
      (node (ref "R23") (pin "1") (pinfunction "1_1") (pintype "passive"))
      (node (ref "R25") (pin "1") (pinfunction "1_1") (pintype "passive"))
      (node (ref "U6") (pin "11") (pinfunction "BS1_11") (pintype "input"))
      (node (ref "U6") (pin "9") (pinfunction "VDD_9") (pintype "power_in"))
    )
    (net (code "62") (name "VDD_3V3_SD") (class "Default")
      (node (ref "C2") (pin "1") (pinfunction "1_1") (pintype "passive"))
      (node (ref "C3") (pin "1") (pinfunction "1_1") (pintype "passive"))
      (node (ref "D1") (pin "2") (pinfunction "2_2") (pintype "bidirectional"))
      (node (ref "FB3") (pin "2") (pinfunction "2_2") (pintype "bidirectional"))
      (node (ref "J3") (pin "4") (pinfunction "VDD_4") (pintype "bidirectional"))
      (node (ref "R60") (pin "2") (pinfunction "2_2") (pintype "passive"))
      (node (ref "R61") (pin "2") (pinfunction "2_2") (pintype "passive"))
      (node (ref "R62") (pin "2") (pinfunction "2_2") (pintype "passive"))
      (node (ref "R63") (pin "2") (pinfunction "2_2") (pintype "passive"))
      (node (ref "R64") (pin "2") (pinfunction "2_2") (pintype "passive"))
    )
    (net (code "63") (name "VSYS") (class "Default")
      (node (ref "C1") (pin "1") (pinfunction "1_1") (pintype "passive"))
      (node (ref "C11") (pin "1") (pinfunction "1_1") (pintype "passive"))
      (node (ref "C14") (pin "1") (pinfunction "1_1") (pintype "passive"))
      (node (ref "C15") (pin "2") (pinfunction "2_2") (pintype "passive"))
      (node (ref "C16") (pin "2") (pinfunction "2_2") (pintype "passive"))
      (node (ref "C18") (pin "1") (pinfunction "1_1") (pintype "passive"))
      (node (ref "C27") (pin "2") (pinfunction "2_2") (pintype "passive"))
      (node (ref "D16") (pin "+") (pinfunction "+_+") (pintype "passive"))
      (node (ref "L1") (pin "1") (pinfunction "1_1") (pintype "passive"))
      (node (ref "L3") (pin "2") (pinfunction "2_2") (pintype "passive"))
      (node (ref "U3") (pin "5") (pinfunction "EN_5") (pintype "bidirectional"))
      (node (ref "U3") (pin "7") (pinfunction "AVIN_7") (pintype "bidirectional"))
      (node (ref "U3") (pin "8") (pinfunction "PVIN_8") (pintype "bidirectional"))
      (node (ref "U4") (pin "3") (pinfunction "EN_3") (pintype "bidirectional"))
      (node (ref "U4") (pin "4") (pinfunction "IN_4") (pintype "bidirectional"))
      (node (ref "U5") (pin "1") (pinfunction "SYS_1") (pintype "bidirectional"))
      (node (ref "U5") (pin "15") (pinfunction "SYS_15") (pintype "bidirectional"))
    )
    (net (code "64") (name "unconnected-(J3-CDN-Pad9)") (class "Default")
      (node (ref "J3") (pin "9") (pinfunction "CDN_9") (pintype "bidirectional"))
    )
    (net (code "65") (name "unconnected-(J5-Pad2)") (class "Default")
      (node (ref "J5") (pin "2") (pinfunction "2_2") (pintype "bidirectional"))
    )
    (net (code "66") (name "unconnected-(JP2-R-Pad00)") (class "Default")
      (node (ref "JP2") (pin "00") (pinfunction "R_00") (pintype "bidirectional"))
    )
    (net (code "67") (name "unconnected-(SW1-PadCH1A)") (class "Default")
      (node (ref "SW1") (pin "CH1A") (pinfunction "CH1A_CH1A") (pintype "bidirectional"))
    )
    (net (code "68") (name "unconnected-(SW1-PadCH2A)") (class "Default")
      (node (ref "SW1") (pin "CH2A") (pinfunction "CH2A_CH2A") (pintype "bidirectional"))
    )
    (net (code "69") (name "unconnected-(U6-BS2-Pad12)") (class "Default")
      (node (ref "U6") (pin "12") (pinfunction "BS2_12") (pintype "input"))
    )
    (net (code "70") (name "unconnected-(U6-D3-Pad21)") (class "Default")
      (node (ref "U6") (pin "21") (pinfunction "D3_21") (pintype "input"))
    )
    (net (code "71") (name "unconnected-(U6-D4-Pad22)") (class "Default")
      (node (ref "U6") (pin "22") (pinfunction "D4_22") (pintype "input"))
    )
    (net (code "72") (name "unconnected-(U6-D5-Pad23)") (class "Default")
      (node (ref "U6") (pin "23") (pinfunction "D5_23") (pintype "input"))
    )
    (net (code "73") (name "unconnected-(U6-D6-Pad24)") (class "Default")
      (node (ref "U6") (pin "24") (pinfunction "D6_24") (pintype "input"))
    )
    (net (code "74") (name "unconnected-(U6-D7-Pad25)") (class "Default")
      (node (ref "U6") (pin "25") (pinfunction "D7_25") (pintype "input"))
    )
    (net (code "75") (name "unconnected-(U6-E{slash}RD-Pad17)") (class "Default")
      (node (ref "U6") (pin "17") (pinfunction "E/RD_17") (pintype "input"))
    )
    (net (code "76") (name "unconnected-(U6-NC-Pad7)") (class "Default")
      (node (ref "U6") (pin "7") (pinfunction "NC_7") (pintype "no_connect"))
    )
    (net (code "77") (name "unconnected-(U6-R{slash}W-Pad16)") (class "Default")
      (node (ref "U6") (pin "16") (pinfunction "R/W_16") (pintype "input"))
    )
  )
)
